# BUS_OUT.net
KiCad netlist of a schematic drawn in EAGLE
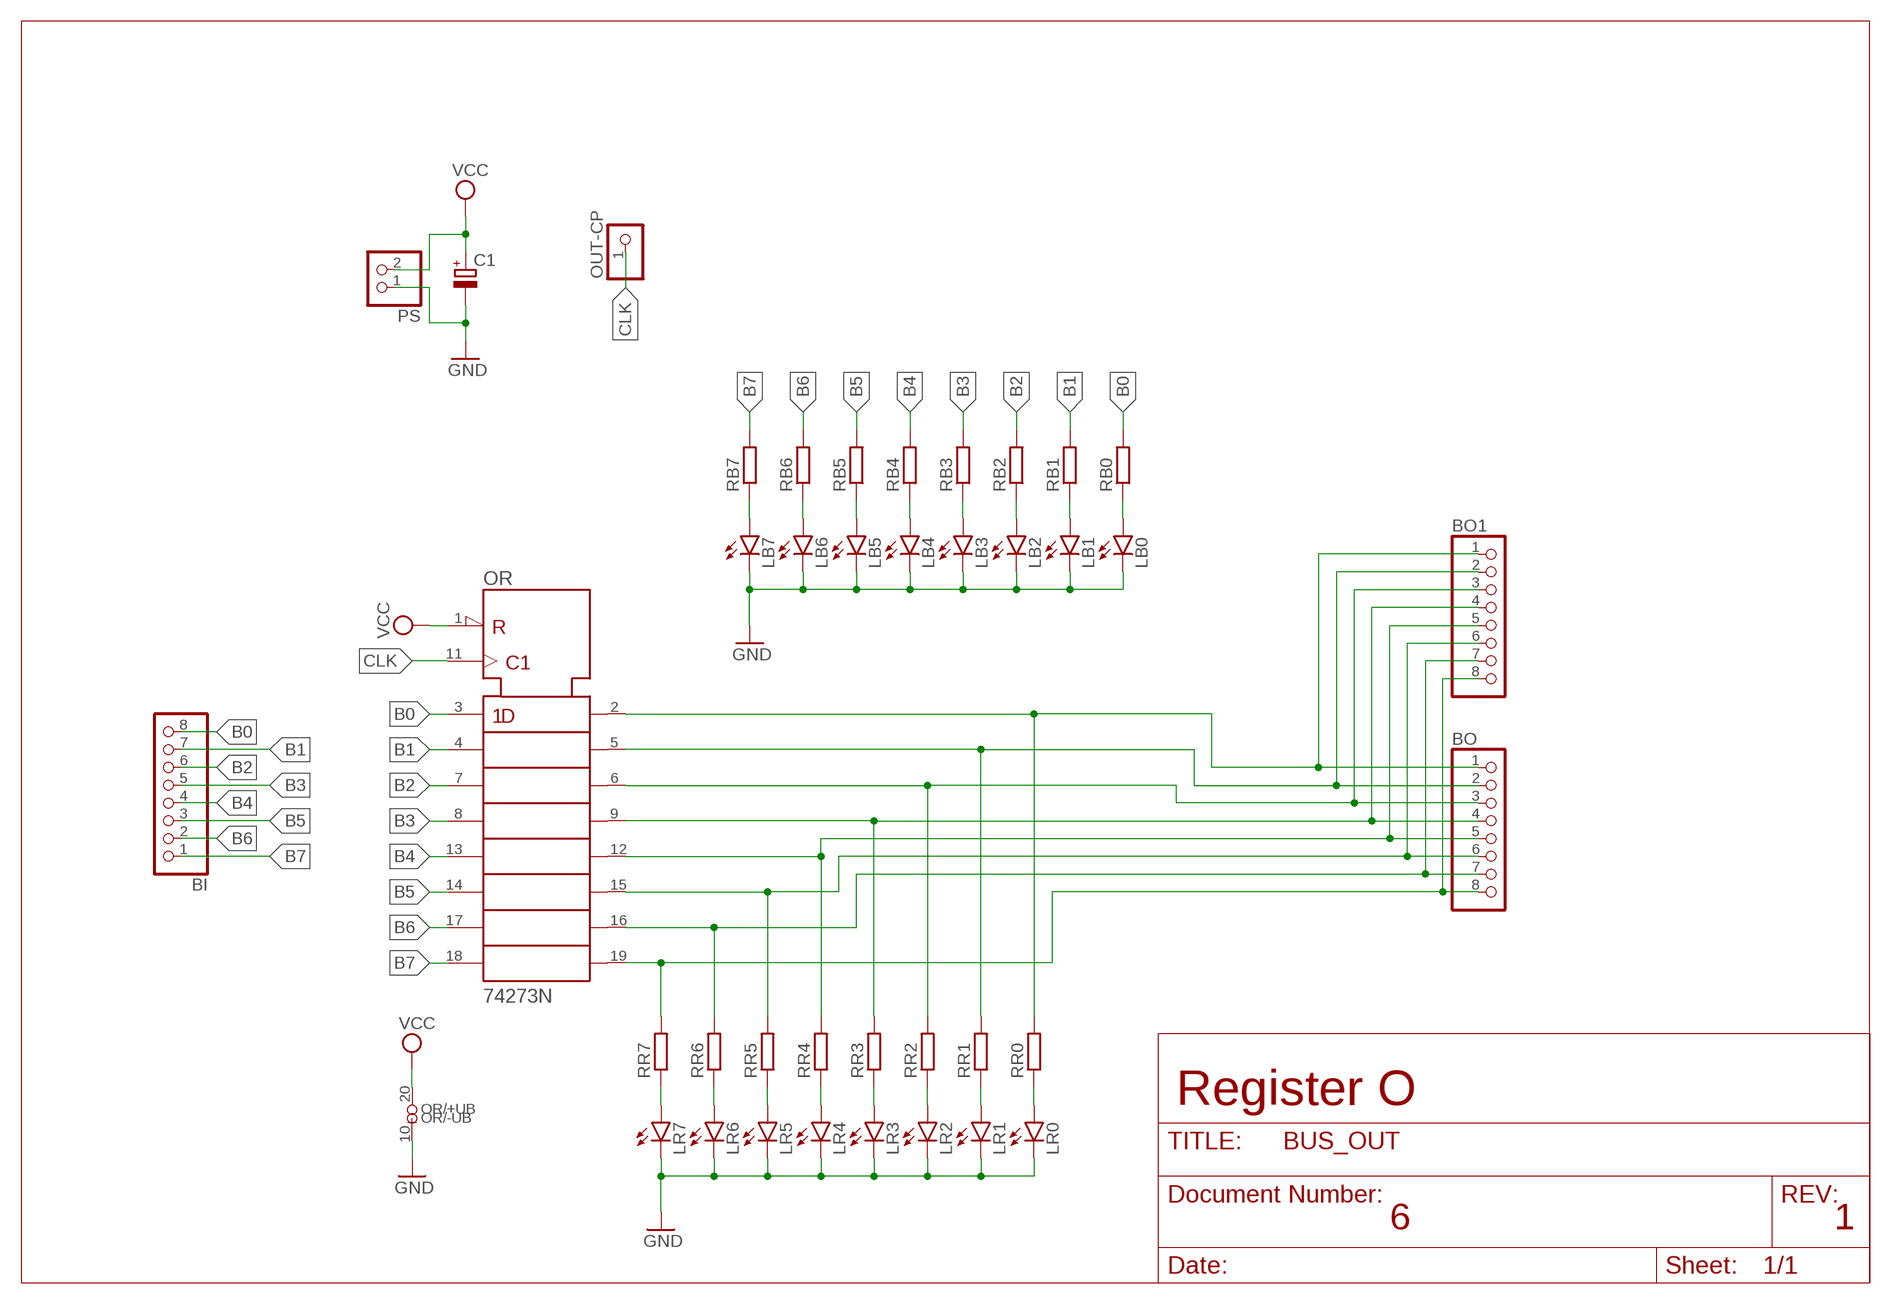
[diagram p0: schematic, sheet 1]

(export (version "E")
  (design (tool "Eeschema 10.0.6"))
  (components
    (comp (ref "BI")
      (value "PINHD-1X8")
      (footprint "eagle-import:1X08")
      (libsource (lib "eagle-import") (part "PINHD-1X8"))
    )
    (comp (ref "BO")
      (value "PINHD-1X8")
      (footprint "eagle-import:1X08")
      (libsource (lib "eagle-import") (part "PINHD-1X8"))
    )
    (comp (ref "BO1")
      (value "PINHD-1X8")
      (footprint "eagle-import:1X08")
      (libsource (lib "eagle-import") (part "PINHD-1X8"))
    )
    (comp (ref "C1")
      (value "CPOL-EUE2.5-6")
      (footprint "eagle-import:E2,5-6")
      (libsource (lib "eagle-import") (part "CPOL-EUE2.5-6"))
    )
    (comp (ref "LB0")
      (value "LED5MM")
      (footprint "eagle-import:LED5MM")
      (libsource (lib "eagle-import") (part "LED5MM"))
    )
    (comp (ref "LB1")
      (value "LED5MM")
      (footprint "eagle-import:LED5MM")
      (libsource (lib "eagle-import") (part "LED5MM"))
    )
    (comp (ref "LB2")
      (value "LED5MM")
      (footprint "eagle-import:LED5MM")
      (libsource (lib "eagle-import") (part "LED5MM"))
    )
    (comp (ref "LB3")
      (value "LED5MM")
      (footprint "eagle-import:LED5MM")
      (libsource (lib "eagle-import") (part "LED5MM"))
    )
    (comp (ref "LB4")
      (value "LED5MM")
      (footprint "eagle-import:LED5MM")
      (libsource (lib "eagle-import") (part "LED5MM"))
    )
    (comp (ref "LB5")
      (value "LED5MM")
      (footprint "eagle-import:LED5MM")
      (libsource (lib "eagle-import") (part "LED5MM"))
    )
    (comp (ref "LB6")
      (value "LED5MM")
      (footprint "eagle-import:LED5MM")
      (libsource (lib "eagle-import") (part "LED5MM"))
    )
    (comp (ref "LB7")
      (value "LED5MM")
      (footprint "eagle-import:LED5MM")
      (libsource (lib "eagle-import") (part "LED5MM"))
    )
    (comp (ref "LR0")
      (value "LED5MM")
      (footprint "eagle-import:LED5MM")
      (libsource (lib "eagle-import") (part "LED5MM"))
    )
    (comp (ref "LR1")
      (value "LED5MM")
      (footprint "eagle-import:LED5MM")
      (libsource (lib "eagle-import") (part "LED5MM"))
    )
    (comp (ref "LR2")
      (value "LED5MM")
      (footprint "eagle-import:LED5MM")
      (libsource (lib "eagle-import") (part "LED5MM"))
    )
    (comp (ref "LR3")
      (value "LED5MM")
      (footprint "eagle-import:LED5MM")
      (libsource (lib "eagle-import") (part "LED5MM"))
    )
    (comp (ref "LR4")
      (value "LED5MM")
      (footprint "eagle-import:LED5MM")
      (libsource (lib "eagle-import") (part "LED5MM"))
    )
    (comp (ref "LR5")
      (value "LED5MM")
      (footprint "eagle-import:LED5MM")
      (libsource (lib "eagle-import") (part "LED5MM"))
    )
    (comp (ref "LR6")
      (value "LED5MM")
      (footprint "eagle-import:LED5MM")
      (libsource (lib "eagle-import") (part "LED5MM"))
    )
    (comp (ref "LR7")
      (value "LED5MM")
      (footprint "eagle-import:LED5MM")
      (libsource (lib "eagle-import") (part "LED5MM"))
    )
    (comp (ref "OR")
      (value "74273N")
      (footprint "eagle-import:DIL20")
      (libsource (lib "eagle-import") (part "74273N"))
    )
    (comp (ref "OUT-CP")
      (value "PINHD-1X1")
      (footprint "eagle-import:1X01")
      (libsource (lib "eagle-import") (part "PINHD-1X1"))
    )
    (comp (ref "PS")
      (value "PINHD-1X2")
      (footprint "eagle-import:1X02")
      (libsource (lib "eagle-import") (part "PINHD-1X2"))
    )
    (comp (ref "RB0")
      (value "R-EU_0204/7")
      (footprint "eagle-import:0204_7")
      (libsource (lib "eagle-import") (part "R-EU_0204/7"))
    )
    (comp (ref "RB1")
      (value "R-EU_0204/7")
      (footprint "eagle-import:0204_7")
      (libsource (lib "eagle-import") (part "R-EU_0204/7"))
    )
    (comp (ref "RB2")
      (value "R-EU_0204/7")
      (footprint "eagle-import:0204_7")
      (libsource (lib "eagle-import") (part "R-EU_0204/7"))
    )
    (comp (ref "RB3")
      (value "R-EU_0204/7")
      (footprint "eagle-import:0204_7")
      (libsource (lib "eagle-import") (part "R-EU_0204/7"))
    )
    (comp (ref "RB4")
      (value "R-EU_0204/7")
      (footprint "eagle-import:0204_7")
      (libsource (lib "eagle-import") (part "R-EU_0204/7"))
    )
    (comp (ref "RB5")
      (value "R-EU_0204/7")
      (footprint "eagle-import:0204_7")
      (libsource (lib "eagle-import") (part "R-EU_0204/7"))
    )
    (comp (ref "RB6")
      (value "R-EU_0204/7")
      (footprint "eagle-import:0204_7")
      (libsource (lib "eagle-import") (part "R-EU_0204/7"))
    )
    (comp (ref "RB7")
      (value "R-EU_0204/7")
      (footprint "eagle-import:0204_7")
      (libsource (lib "eagle-import") (part "R-EU_0204/7"))
    )
    (comp (ref "RR0")
      (value "R-EU_0204/7")
      (footprint "eagle-import:0204_7")
      (libsource (lib "eagle-import") (part "R-EU_0204/7"))
    )
    (comp (ref "RR1")
      (value "R-EU_0204/7")
      (footprint "eagle-import:0204_7")
      (libsource (lib "eagle-import") (part "R-EU_0204/7"))
    )
    (comp (ref "RR2")
      (value "R-EU_0204/7")
      (footprint "eagle-import:0204_7")
      (libsource (lib "eagle-import") (part "R-EU_0204/7"))
    )
    (comp (ref "RR3")
      (value "R-EU_0204/7")
      (footprint "eagle-import:0204_7")
      (libsource (lib "eagle-import") (part "R-EU_0204/7"))
    )
    (comp (ref "RR4")
      (value "R-EU_0204/7")
      (footprint "eagle-import:0204_7")
      (libsource (lib "eagle-import") (part "R-EU_0204/7"))
    )
    (comp (ref "RR5")
      (value "R-EU_0204/7")
      (footprint "eagle-import:0204_7")
      (libsource (lib "eagle-import") (part "R-EU_0204/7"))
    )
    (comp (ref "RR6")
      (value "R-EU_0204/7")
      (footprint "eagle-import:0204_7")
      (libsource (lib "eagle-import") (part "R-EU_0204/7"))
    )
    (comp (ref "RR7")
      (value "R-EU_0204/7")
      (footprint "eagle-import:0204_7")
      (libsource (lib "eagle-import") (part "R-EU_0204/7"))
    )
  )
  (nets
    (net (code "1") (name "B0") (class "Default")
      (node (ref "BI") (pin "8") (pinfunction "8_8") (pintype "passive"))
      (node (ref "OR") (pin "3") (pinfunction "1D_3") (pintype "input"))
      (node (ref "RB0") (pin "2") (pinfunction "2_2") (pintype "passive"))
    )
    (net (code "2") (name "B1") (class "Default")
      (node (ref "BI") (pin "7") (pinfunction "7_7") (pintype "passive"))
      (node (ref "OR") (pin "4") (pinfunction "2D_4") (pintype "input"))
      (node (ref "RB1") (pin "2") (pinfunction "2_2") (pintype "passive"))
    )
    (net (code "3") (name "B2") (class "Default")
      (node (ref "BI") (pin "6") (pinfunction "6_6") (pintype "passive"))
      (node (ref "OR") (pin "7") (pinfunction "3D_7") (pintype "input"))
      (node (ref "RB2") (pin "2") (pinfunction "2_2") (pintype "passive"))
    )
    (net (code "4") (name "B3") (class "Default")
      (node (ref "BI") (pin "5") (pinfunction "5_5") (pintype "passive"))
      (node (ref "OR") (pin "8") (pinfunction "4D_8") (pintype "input"))
      (node (ref "RB3") (pin "2") (pinfunction "2_2") (pintype "passive"))
    )
    (net (code "5") (name "B4") (class "Default")
      (node (ref "BI") (pin "4") (pinfunction "4_4") (pintype "passive"))
      (node (ref "OR") (pin "13") (pinfunction "5D_13") (pintype "input"))
      (node (ref "RB4") (pin "2") (pinfunction "2_2") (pintype "passive"))
    )
    (net (code "6") (name "B5") (class "Default")
      (node (ref "BI") (pin "3") (pinfunction "3_3") (pintype "passive"))
      (node (ref "OR") (pin "14") (pinfunction "6D_14") (pintype "input"))
      (node (ref "RB5") (pin "2") (pinfunction "2_2") (pintype "passive"))
    )
    (net (code "7") (name "B6") (class "Default")
      (node (ref "BI") (pin "2") (pinfunction "2_2") (pintype "passive"))
      (node (ref "OR") (pin "17") (pinfunction "7D_17") (pintype "input"))
      (node (ref "RB6") (pin "2") (pinfunction "2_2") (pintype "passive"))
    )
    (net (code "8") (name "B7") (class "Default")
      (node (ref "BI") (pin "1") (pinfunction "1_1") (pintype "passive"))
      (node (ref "OR") (pin "18") (pinfunction "8D_18") (pintype "input"))
      (node (ref "RB7") (pin "2") (pinfunction "2_2") (pintype "passive"))
    )
    (net (code "9") (name "CLK") (class "Default")
      (node (ref "OR") (pin "11") (pinfunction "CLK_11") (pintype "input"))
      (node (ref "OUT-CP") (pin "1") (pinfunction "1_1") (pintype "passive"))
    )
    (net (code "10") (name "GND") (class "Default")
      (node (ref "C1") (pin "-") (pinfunction "-_-") (pintype "passive"))
      (node (ref "LB0") (pin "K") (pinfunction "C_K") (pintype "passive"))
      (node (ref "LB1") (pin "K") (pinfunction "C_K") (pintype "passive"))
      (node (ref "LB2") (pin "K") (pinfunction "C_K") (pintype "passive"))
      (node (ref "LB3") (pin "K") (pinfunction "C_K") (pintype "passive"))
      (node (ref "LB4") (pin "K") (pinfunction "C_K") (pintype "passive"))
      (node (ref "LB5") (pin "K") (pinfunction "C_K") (pintype "passive"))
      (node (ref "LB6") (pin "K") (pinfunction "C_K") (pintype "passive"))
      (node (ref "LB7") (pin "K") (pinfunction "C_K") (pintype "passive"))
      (node (ref "LR0") (pin "K") (pinfunction "C_K") (pintype "passive"))
      (node (ref "LR1") (pin "K") (pinfunction "C_K") (pintype "passive"))
      (node (ref "LR2") (pin "K") (pinfunction "C_K") (pintype "passive"))
      (node (ref "LR3") (pin "K") (pinfunction "C_K") (pintype "passive"))
      (node (ref "LR4") (pin "K") (pinfunction "C_K") (pintype "passive"))
      (node (ref "LR5") (pin "K") (pinfunction "C_K") (pintype "passive"))
      (node (ref "LR6") (pin "K") (pinfunction "C_K") (pintype "passive"))
      (node (ref "LR7") (pin "K") (pinfunction "C_K") (pintype "passive"))
      (node (ref "OR") (pin "10") (pinfunction "-UB_10") (pintype "power_in"))
      (node (ref "PS") (pin "1") (pinfunction "1_1") (pintype "passive"))
    )
    (net (code "11") (name "Net-(LB0-PadA)") (class "Default")
      (node (ref "LB0") (pin "A") (pinfunction "A_A") (pintype "passive"))
      (node (ref "RB0") (pin "1") (pinfunction "1_1") (pintype "passive"))
    )
    (net (code "12") (name "Net-(LB1-PadA)") (class "Default")
      (node (ref "LB1") (pin "A") (pinfunction "A_A") (pintype "passive"))
      (node (ref "RB1") (pin "1") (pinfunction "1_1") (pintype "passive"))
    )
    (net (code "13") (name "Net-(LB2-PadA)") (class "Default")
      (node (ref "LB2") (pin "A") (pinfunction "A_A") (pintype "passive"))
      (node (ref "RB2") (pin "1") (pinfunction "1_1") (pintype "passive"))
    )
    (net (code "14") (name "Net-(LB3-PadA)") (class "Default")
      (node (ref "LB3") (pin "A") (pinfunction "A_A") (pintype "passive"))
      (node (ref "RB3") (pin "1") (pinfunction "1_1") (pintype "passive"))
    )
    (net (code "15") (name "Net-(LB4-PadA)") (class "Default")
      (node (ref "LB4") (pin "A") (pinfunction "A_A") (pintype "passive"))
      (node (ref "RB4") (pin "1") (pinfunction "1_1") (pintype "passive"))
    )
    (net (code "16") (name "Net-(LB5-PadA)") (class "Default")
      (node (ref "LB5") (pin "A") (pinfunction "A_A") (pintype "passive"))
      (node (ref "RB5") (pin "1") (pinfunction "1_1") (pintype "passive"))
    )
    (net (code "17") (name "Net-(LB6-PadA)") (class "Default")
      (node (ref "LB6") (pin "A") (pinfunction "A_A") (pintype "passive"))
      (node (ref "RB6") (pin "1") (pinfunction "1_1") (pintype "passive"))
    )
    (net (code "18") (name "Net-(LB7-PadA)") (class "Default")
      (node (ref "LB7") (pin "A") (pinfunction "A_A") (pintype "passive"))
      (node (ref "RB7") (pin "1") (pinfunction "1_1") (pintype "passive"))
    )
    (net (code "19") (name "Net-(LR0-PadA)") (class "Default")
      (node (ref "LR0") (pin "A") (pinfunction "A_A") (pintype "passive"))
      (node (ref "RR0") (pin "1") (pinfunction "1_1") (pintype "passive"))
    )
    (net (code "20") (name "Net-(LR1-PadA)") (class "Default")
      (node (ref "LR1") (pin "A") (pinfunction "A_A") (pintype "passive"))
      (node (ref "RR1") (pin "1") (pinfunction "1_1") (pintype "passive"))
    )
    (net (code "21") (name "Net-(LR2-PadA)") (class "Default")
      (node (ref "LR2") (pin "A") (pinfunction "A_A") (pintype "passive"))
      (node (ref "RR2") (pin "1") (pinfunction "1_1") (pintype "passive"))
    )
    (net (code "22") (name "Net-(LR3-PadA)") (class "Default")
      (node (ref "LR3") (pin "A") (pinfunction "A_A") (pintype "passive"))
      (node (ref "RR3") (pin "1") (pinfunction "1_1") (pintype "passive"))
    )
    (net (code "23") (name "Net-(LR4-PadA)") (class "Default")
      (node (ref "LR4") (pin "A") (pinfunction "A_A") (pintype "passive"))
      (node (ref "RR4") (pin "1") (pinfunction "1_1") (pintype "passive"))
    )
    (net (code "24") (name "Net-(LR5-PadA)") (class "Default")
      (node (ref "LR5") (pin "A") (pinfunction "A_A") (pintype "passive"))
      (node (ref "RR5") (pin "1") (pinfunction "1_1") (pintype "passive"))
    )
    (net (code "25") (name "Net-(LR6-PadA)") (class "Default")
      (node (ref "LR6") (pin "A") (pinfunction "A_A") (pintype "passive"))
      (node (ref "RR6") (pin "1") (pinfunction "1_1") (pintype "passive"))
    )
    (net (code "26") (name "Net-(LR7-PadA)") (class "Default")
      (node (ref "LR7") (pin "A") (pinfunction "A_A") (pintype "passive"))
      (node (ref "RR7") (pin "1") (pinfunction "1_1") (pintype "passive"))
    )
    (net (code "27") (name "Net-(ORC-1Q)") (class "Default")
      (node (ref "BO") (pin "1") (pinfunction "1_1") (pintype "passive"))
      (node (ref "BO1") (pin "1") (pinfunction "1_1") (pintype "passive"))
      (node (ref "OR") (pin "2") (pinfunction "1Q_2") (pintype "output"))
      (node (ref "RR0") (pin "2") (pinfunction "2_2") (pintype "passive"))
    )
    (net (code "28") (name "Net-(ORC-2Q)") (class "Default")
      (node (ref "BO") (pin "2") (pinfunction "2_2") (pintype "passive"))
      (node (ref "BO1") (pin "2") (pinfunction "2_2") (pintype "passive"))
      (node (ref "OR") (pin "5") (pinfunction "2Q_5") (pintype "output"))
      (node (ref "RR1") (pin "2") (pinfunction "2_2") (pintype "passive"))
    )
    (net (code "29") (name "Net-(ORC-3Q)") (class "Default")
      (node (ref "BO") (pin "3") (pinfunction "3_3") (pintype "passive"))
      (node (ref "BO1") (pin "3") (pinfunction "3_3") (pintype "passive"))
      (node (ref "OR") (pin "6") (pinfunction "3Q_6") (pintype "output"))
      (node (ref "RR2") (pin "2") (pinfunction "2_2") (pintype "passive"))
    )
    (net (code "30") (name "Net-(ORC-4Q)") (class "Default")
      (node (ref "BO") (pin "4") (pinfunction "4_4") (pintype "passive"))
      (node (ref "BO1") (pin "4") (pinfunction "4_4") (pintype "passive"))
      (node (ref "OR") (pin "9") (pinfunction "4Q_9") (pintype "output"))
      (node (ref "RR3") (pin "2") (pinfunction "2_2") (pintype "passive"))
    )
    (net (code "31") (name "Net-(ORC-5Q)") (class "Default")
      (node (ref "BO") (pin "5") (pinfunction "5_5") (pintype "passive"))
      (node (ref "BO1") (pin "5") (pinfunction "5_5") (pintype "passive"))
      (node (ref "OR") (pin "12") (pinfunction "5Q_12") (pintype "output"))
      (node (ref "RR4") (pin "2") (pinfunction "2_2") (pintype "passive"))
    )
    (net (code "32") (name "Net-(ORC-6Q)") (class "Default")
      (node (ref "BO") (pin "6") (pinfunction "6_6") (pintype "passive"))
      (node (ref "BO1") (pin "6") (pinfunction "6_6") (pintype "passive"))
      (node (ref "OR") (pin "15") (pinfunction "6Q_15") (pintype "output"))
      (node (ref "RR5") (pin "2") (pinfunction "2_2") (pintype "passive"))
    )
    (net (code "33") (name "Net-(ORC-7Q)") (class "Default")
      (node (ref "BO") (pin "7") (pinfunction "7_7") (pintype "passive"))
      (node (ref "BO1") (pin "7") (pinfunction "7_7") (pintype "passive"))
      (node (ref "OR") (pin "16") (pinfunction "7Q_16") (pintype "output"))
      (node (ref "RR6") (pin "2") (pinfunction "2_2") (pintype "passive"))
    )
    (net (code "34") (name "Net-(ORC-8Q)") (class "Default")
      (node (ref "BO") (pin "8") (pinfunction "8_8") (pintype "passive"))
      (node (ref "BO1") (pin "8") (pinfunction "8_8") (pintype "passive"))
      (node (ref "OR") (pin "19") (pinfunction "8Q_19") (pintype "output"))
      (node (ref "RR7") (pin "2") (pinfunction "2_2") (pintype "passive"))
    )
    (net (code "35") (name "VCC") (class "Default")
      (node (ref "C1") (pin "+") (pinfunction "+_+") (pintype "passive"))
      (node (ref "OR") (pin "1") (pinfunction "~{CLR}_1") (pintype "input"))
      (node (ref "OR") (pin "20") (pinfunction "+UB_20") (pintype "power_in"))
      (node (ref "PS") (pin "2") (pinfunction "2_2") (pintype "passive"))
    )
  )
)
